# FM_module_TEA5767.net
KiCad netlist of a schematic drawn in EAGLE
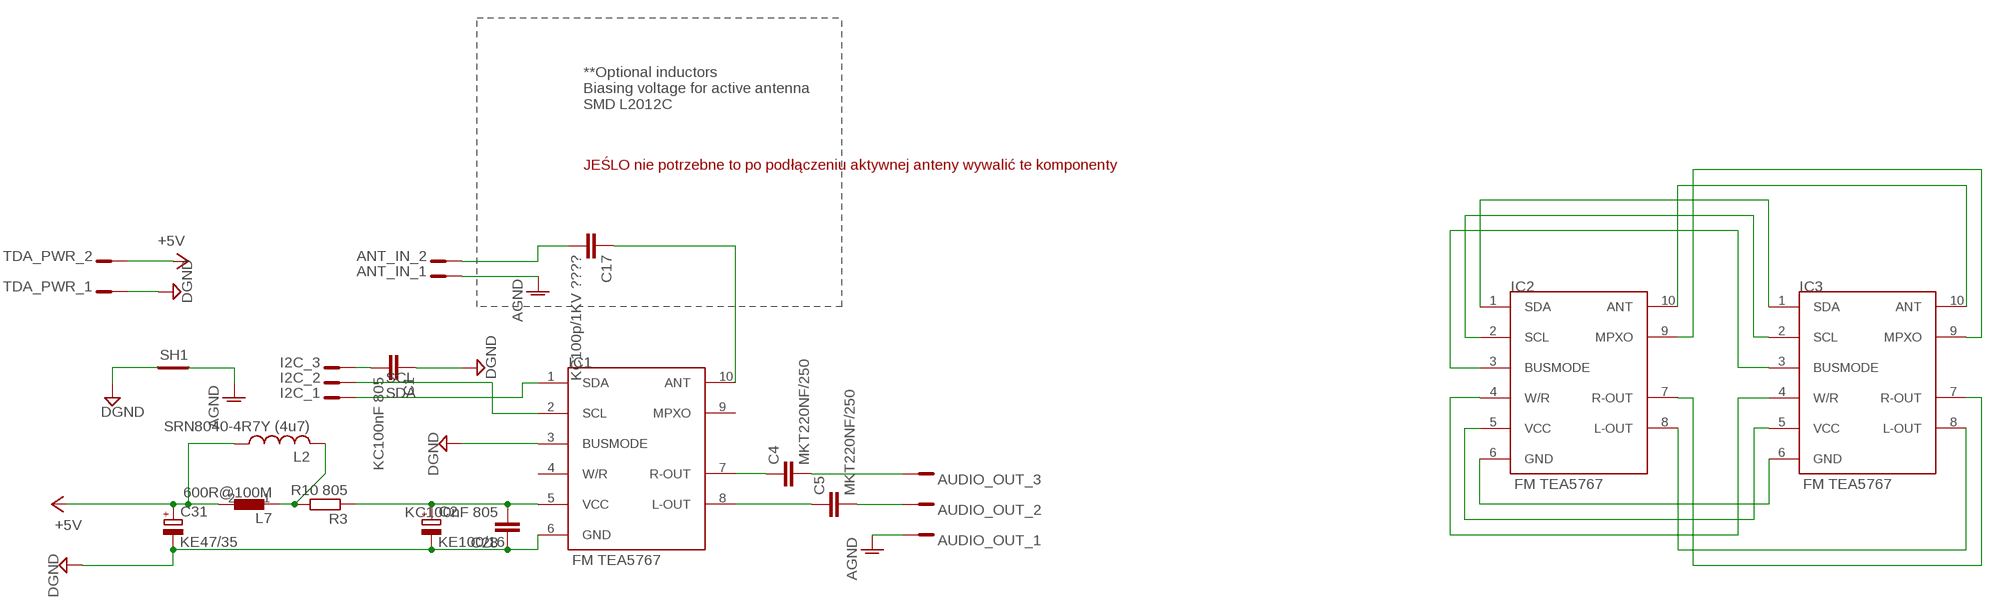
[diagram p0: schematic, sheet 1]

(export (version "E")
  (design (tool "Eeschema 10.0.6"))
  (components
    (comp (ref "ANT_IN")
      (value "JST_2_PIN_B2B-PH-KS")
      (footprint "eagle-import:B2B-PH-KS")
      (libsource (lib "eagle-import") (part "JST_2_PIN_B2B-PH-KS"))
    )
    (comp (ref "AUDIO_OUT")
      (value "JST_3_PIN_B3B-PH-KS")
      (footprint "eagle-import:B3B-PH-KS")
      (libsource (lib "eagle-import") (part "JST_3_PIN_B3B-PH-KS"))
    )
    (comp (ref "C1")
      (value "KC100nF 805")
      (footprint "eagle-import:C0805")
      (libsource (lib "eagle-import") (part "C-EUC0805"))
    )
    (comp (ref "C2")
      (value "KE100/16")
      (footprint "eagle-import:TT2D6")
      (libsource (lib "eagle-import") (part "CPOL-EUTT2D6"))
    )
    (comp (ref "C4")
      (value "MKT220NF/250")
      (footprint "eagle-import:C050-050X075")
      (libsource (lib "eagle-import") (part "C-EU050-050X075"))
    )
    (comp (ref "C5")
      (value "MKT220NF/250")
      (footprint "eagle-import:C050-050X075")
      (libsource (lib "eagle-import") (part "C-EU050-050X075"))
    )
    (comp (ref "C17")
      (value "KC100p/1KV ????")
      (footprint "eagle-import:C050-025X075")
      (libsource (lib "eagle-import") (part "C-EU050-025X075"))
    )
    (comp (ref "C28")
      (value "KC100nF 805")
      (footprint "eagle-import:C0805")
      (libsource (lib "eagle-import") (part "C-EUC0805"))
    )
    (comp (ref "C31")
      (value "KE47/35")
      (footprint "eagle-import:TT2D6")
      (libsource (lib "eagle-import") (part "CPOL-EUTT2D6"))
    )
    (comp (ref "I2C")
      (value "JST_3_PIN_B3B-PH-KS")
      (footprint "eagle-import:B3B-PH-KS")
      (libsource (lib "eagle-import") (part "JST_3_PIN_B3B-PH-KS"))
    )
    (comp (ref "IC1")
      (value "FM TEA5767")
      (footprint "eagle-import:PROTOTYPE")
      (libsource (lib "eagle-import") (part "TEA5767_MODULE_2.54MM"))
    )
    (comp (ref "IC2")
      (value "FM TEA5767")
      (footprint "eagle-import:PROTOTYPE")
      (libsource (lib "eagle-import") (part "TEA5767_MODULE_2.54MM"))
    )
    (comp (ref "IC3")
      (value "FM TEA5767")
      (footprint "eagle-import:SMD")
      (libsource (lib "eagle-import") (part "TEA5767_MODULE_SMD"))
    )
    (comp (ref "L2")
      (value "SRN8040-4R7Y (4u7)")
      (footprint "eagle-import:0204_5")
      (libsource (lib "eagle-import") (part "L-US0204/5"))
    )
    (comp (ref "L7")
      (value "600R@100M")
      (footprint "eagle-import:R0805")
      (libsource (lib "eagle-import") (part "FERRITR0805"))
    )
    (comp (ref "R3")
      (value "R10 805")
      (footprint "eagle-import:R0805")
      (libsource (lib "eagle-import") (part "R-EU_R0805"))
    )
    (comp (ref "SH1")
      (value "SHORT-HT5")
      (footprint "eagle-import:SHORT_TOP-50")
      (libsource (lib "eagle-import") (part "SHORT-HT5"))
    )
    (comp (ref "TDA_PWR")
      (value "JST_2_PIN_B2B-XH-A")
      (footprint "eagle-import:B2B-XH-A")
      (libsource (lib "eagle-import") (part "JST_2_PIN_B2B-XH-A"))
    )
  )
  (nets
    (net (code "1") (name "+5V") (class "Default")
      (node (ref "C31") (pin "+") (pinfunction "+_+") (pintype "passive"))
      (node (ref "L2") (pin "1") (pinfunction "1_1") (pintype "passive"))
      (node (ref "L7") (pin "2") (pinfunction "2_2") (pintype "passive"))
      (node (ref "TDA_PWR") (pin "P$2") (pinfunction "P$1_P$2") (pintype "bidirectional"))
    )
    (net (code "2") (name "/SCL") (class "Default")
      (node (ref "I2C") (pin "P$2") (pinfunction "P$1_P$2") (pintype "bidirectional"))
      (node (ref "IC1") (pin "2") (pinfunction "SCL_2") (pintype "bidirectional"))
    )
    (net (code "3") (name "/SDA") (class "Default")
      (node (ref "I2C") (pin "P$1") (pinfunction "P$1_P$1") (pintype "bidirectional"))
      (node (ref "IC1") (pin "1") (pinfunction "SDA_1") (pintype "bidirectional"))
    )
    (net (code "4") (name "AGND") (class "Default")
      (node (ref "ANT_IN") (pin "P$1") (pinfunction "P$1_P$1") (pintype "bidirectional"))
      (node (ref "AUDIO_OUT") (pin "P$1") (pinfunction "P$1_P$1") (pintype "bidirectional"))
      (node (ref "SH1") (pin "2") (pinfunction "P$2_2") (pintype "bidirectional"))
    )
    (net (code "5") (name "DGND") (class "Default")
      (node (ref "C1") (pin "1") (pinfunction "1_1") (pintype "passive"))
      (node (ref "C2") (pin "-") (pinfunction "-_-") (pintype "passive"))
      (node (ref "C28") (pin "1") (pinfunction "1_1") (pintype "passive"))
      (node (ref "C31") (pin "-") (pinfunction "-_-") (pintype "passive"))
      (node (ref "IC1") (pin "3") (pinfunction "BUSMODE_3") (pintype "input"))
      (node (ref "IC1") (pin "6") (pinfunction "GND_6") (pintype "power_in"))
      (node (ref "SH1") (pin "1") (pinfunction "P$1_1") (pintype "bidirectional"))
      (node (ref "TDA_PWR") (pin "P$1") (pinfunction "P$1_P$1") (pintype "bidirectional"))
    )
    (net (code "6") (name "Net-(ANT_INB-P$1)") (class "Default")
      (node (ref "ANT_IN") (pin "P$2") (pinfunction "P$1_P$2") (pintype "bidirectional"))
      (node (ref "C17") (pin "2") (pinfunction "2_2") (pintype "passive"))
    )
    (net (code "7") (name "Net-(AUDIO_OUTB-P$1)") (class "Default")
      (node (ref "AUDIO_OUT") (pin "P$2") (pinfunction "P$1_P$2") (pintype "bidirectional"))
      (node (ref "C5") (pin "2") (pinfunction "2_2") (pintype "passive"))
    )
    (net (code "8") (name "Net-(AUDIO_OUTC-P$1)") (class "Default")
      (node (ref "AUDIO_OUT") (pin "P$3") (pinfunction "P$1_P$3") (pintype "bidirectional"))
      (node (ref "C4") (pin "2") (pinfunction "2_2") (pintype "passive"))
    )
    (net (code "9") (name "Net-(I2CC-P$1)") (class "Default")
      (node (ref "C1") (pin "2") (pinfunction "2_2") (pintype "passive"))
      (node (ref "I2C") (pin "P$3") (pinfunction "P$1_P$3") (pintype "bidirectional"))
    )
    (net (code "10") (name "Net-(IC1-ANT)") (class "Default")
      (node (ref "C17") (pin "1") (pinfunction "1_1") (pintype "passive"))
      (node (ref "IC1") (pin "10") (pinfunction "ANT_10") (pintype "input"))
    )
    (net (code "11") (name "Net-(IC1-L-OUT)") (class "Default")
      (node (ref "C5") (pin "1") (pinfunction "1_1") (pintype "passive"))
      (node (ref "IC1") (pin "8") (pinfunction "L-OUT_8") (pintype "output"))
    )
    (net (code "12") (name "Net-(IC1-R-OUT)") (class "Default")
      (node (ref "C4") (pin "1") (pinfunction "1_1") (pintype "passive"))
      (node (ref "IC1") (pin "7") (pinfunction "R-OUT_7") (pintype "output"))
    )
    (net (code "13") (name "Net-(IC1-VCC)") (class "Default")
      (node (ref "C2") (pin "+") (pinfunction "+_+") (pintype "passive"))
      (node (ref "C28") (pin "2") (pinfunction "2_2") (pintype "passive"))
      (node (ref "IC1") (pin "5") (pinfunction "VCC_5") (pintype "power_in"))
      (node (ref "R3") (pin "1") (pinfunction "1_1") (pintype "passive"))
    )
    (net (code "14") (name "Net-(IC2-ANT)") (class "Default")
      (node (ref "IC2") (pin "10") (pinfunction "ANT_10") (pintype "input"))
      (node (ref "IC3") (pin "10") (pinfunction "ANT_10") (pintype "input"))
    )
    (net (code "15") (name "Net-(IC2-BUSMODE)") (class "Default")
      (node (ref "IC2") (pin "3") (pinfunction "BUSMODE_3") (pintype "input"))
      (node (ref "IC3") (pin "3") (pinfunction "BUSMODE_3") (pintype "input"))
    )
    (net (code "16") (name "Net-(IC2-GND)") (class "Default")
      (node (ref "IC2") (pin "6") (pinfunction "GND_6") (pintype "power_in"))
      (node (ref "IC3") (pin "6") (pinfunction "GND_6") (pintype "power_in"))
    )
    (net (code "17") (name "Net-(IC2-L-OUT)") (class "Default")
      (node (ref "IC2") (pin "8") (pinfunction "L-OUT_8") (pintype "output"))
      (node (ref "IC3") (pin "8") (pinfunction "L-OUT_8") (pintype "output"))
    )
    (net (code "18") (name "Net-(IC2-MPXO)") (class "Default")
      (node (ref "IC2") (pin "9") (pinfunction "MPXO_9") (pintype "output"))
      (node (ref "IC3") (pin "9") (pinfunction "MPXO_9") (pintype "output"))
    )
    (net (code "19") (name "Net-(IC2-R-OUT)") (class "Default")
      (node (ref "IC2") (pin "7") (pinfunction "R-OUT_7") (pintype "output"))
      (node (ref "IC3") (pin "7") (pinfunction "R-OUT_7") (pintype "output"))
    )
    (net (code "20") (name "Net-(IC2-SCL)") (class "Default")
      (node (ref "IC2") (pin "2") (pinfunction "SCL_2") (pintype "bidirectional"))
      (node (ref "IC3") (pin "2") (pinfunction "SCL_2") (pintype "bidirectional"))
    )
    (net (code "21") (name "Net-(IC2-SDA)") (class "Default")
      (node (ref "IC2") (pin "1") (pinfunction "SDA_1") (pintype "bidirectional"))
      (node (ref "IC3") (pin "1") (pinfunction "SDA_1") (pintype "bidirectional"))
    )
    (net (code "22") (name "Net-(IC2-VCC)") (class "Default")
      (node (ref "IC2") (pin "5") (pinfunction "VCC_5") (pintype "power_in"))
      (node (ref "IC3") (pin "5") (pinfunction "VCC_5") (pintype "power_in"))
    )
    (net (code "23") (name "Net-(IC2-W{slash}R)") (class "Default")
      (node (ref "IC2") (pin "4") (pinfunction "W/R_4") (pintype "input"))
      (node (ref "IC3") (pin "4") (pinfunction "W/R_4") (pintype "input"))
    )
    (net (code "24") (name "Net-(L2-Pad2)") (class "Default")
      (node (ref "L2") (pin "2") (pinfunction "2_2") (pintype "passive"))
      (node (ref "L7") (pin "1") (pinfunction "1_1") (pintype "passive"))
      (node (ref "R3") (pin "2") (pinfunction "2_2") (pintype "passive"))
    )
    (net (code "25") (name "unconnected-(IC1-MPXO-Pad9)") (class "Default")
      (node (ref "IC1") (pin "9") (pinfunction "MPXO_9") (pintype "output"))
    )
    (net (code "26") (name "unconnected-(IC1-W{slash}R-Pad4)") (class "Default")
      (node (ref "IC1") (pin "4") (pinfunction "W/R_4") (pintype "input"))
    )
  )
)
